# water_system_module.net
KiCad netlist of a schematic drawn in Altium Designer
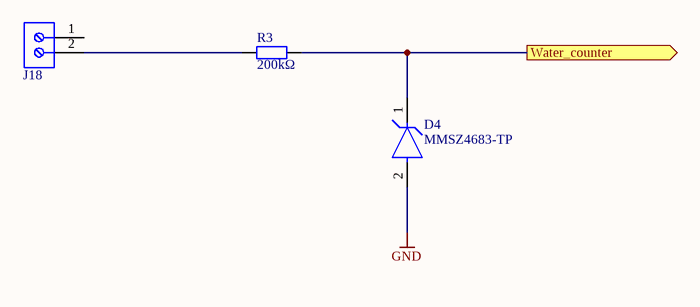
[diagram p0: water_system_module.SchDoc]

(export (version "E")
  (design (tool "Eeschema 10.0.6"))
  (components
    (comp (ref "D4")
      (value "MMSZ4683-TP")
      (footprint "FP-SOD-123-MFG")
      (description "DIODE ZENER 3V 500MW SOD123")
      (fields (field (name "TOLERANCE") "5%"))
      (libsource (lib "Altium Content Vault") (part "f813f71cba58e380607f5dd3caf9714"))
    )
    (comp (ref "J18")
      (value "282836-2")
      (footprint "TECO-282836-2_V")
      (description "Female Header, Pitch 5 mm, 1 x 2 Position, Height 10 mm, Tail Length 3.5 mm, Rohs, Bulk")
      (fields (field (name "VOLTAGE") "300V") (field (name "MANUFACTURER") "TE Connectivity"))
      (libsource (lib "Altium Content Vault") (part "CN-1P-F-TB2"))
    )
    (comp (ref "R3")
      (value "200kΩ")
      (footprint "RESC2013X50X30ML20T20")
      (description "Resistor")
      (libsource (lib "PCB_Project") (part "Res_0805"))
    )
  )
  (nets
    (net (code "1") (name "/Water_counter") (class "Default")
      (node (ref "D4") (pin "1") (pinfunction "C_1") (pintype "passive"))
      (node (ref "R3") (pin "2") (pinfunction "2_2") (pintype "passive"))
    )
    (net (code "2") (name "GND") (class "Default")
      (node (ref "D4") (pin "2") (pinfunction "A_2") (pintype "passive"))
    )
    (net (code "3") (name "Net-(J18-Pad2)") (class "Default")
      (node (ref "J18") (pin "2") (pinfunction "2_2") (pintype "passive"))
      (node (ref "R3") (pin "1") (pinfunction "1_1") (pintype "passive"))
    )
    (net (code "4") (name "unconnected-(J18-Pad1)") (class "Default")
      (node (ref "J18") (pin "1") (pinfunction "1_1") (pintype "passive"))
    )
  )
)
